# AS5600.net
KiCad netlist of a schematic drawn in Altium Designer
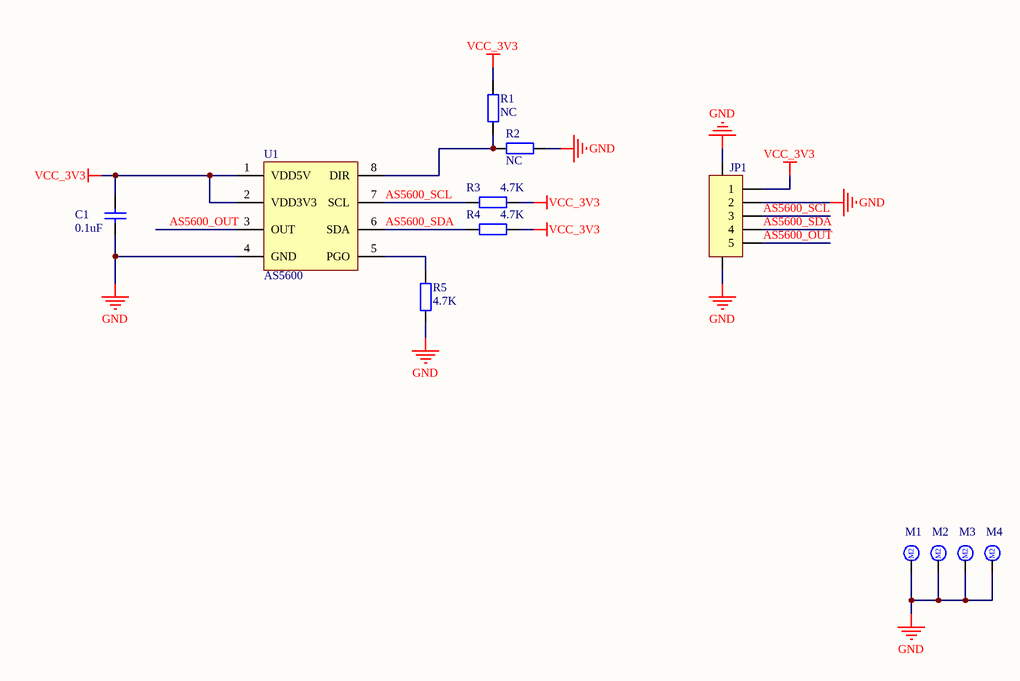
[diagram p0: AS5600.SchDoc]

(export (version "E")
  (design (tool "Eeschema 10.0.6"))
  (components
    (comp (ref "C1")
      (value "0.1uF")
      (footprint "C0402_L")
      (description "贴片电容")
      (libsource (lib "0.1 - 电阻-电容-电感-晶振-晶体-磁珠-电位器") (part "C"))
    )
    (comp (ref "JP1")
      (value "CON-5P")
      (footprint "SH1.0-WT-5P")
      (description "5P连接器")
      (libsource (lib "5.0 - 1.00mm连接器(FPC1.0-SH1.0)") (part "Header 5"))
    )
    (comp (ref "M1")
      (value "M2.5")
      (footprint "M2.5")
      (description "M2孔支撑柱")
      (libsource (lib "USER_Lib") (part "M2系列"))
    )
    (comp (ref "M2")
      (value "M2.5")
      (footprint "M2.5")
      (description "M2孔支撑柱")
      (libsource (lib "USER_Lib") (part "M2系列"))
    )
    (comp (ref "M3")
      (value "M2.5")
      (footprint "M2.5")
      (description "M2孔支撑柱")
      (libsource (lib "USER_Lib") (part "M2系列"))
    )
    (comp (ref "M4")
      (value "M2.5")
      (footprint "M2.5")
      (description "M2孔支撑柱")
      (libsource (lib "USER_Lib") (part "M2系列"))
    )
    (comp (ref "R1")
      (value "NC")
      (footprint "R0402_L")
      (description "贴片电阻")
      (libsource (lib "0.1 - 电阻-电容-电感-晶振-晶体-磁珠-电位器") (part "R"))
    )
    (comp (ref "R2")
      (value "NC")
      (footprint "R0402_L")
      (description "贴片电阻")
      (libsource (lib "0.1 - 电阻-电容-电感-晶振-晶体-磁珠-电位器") (part "R"))
    )
    (comp (ref "R3")
      (value "4.7K")
      (footprint "R0402_L")
      (description "贴片电阻")
      (libsource (lib "0.1 - 电阻-电容-电感-晶振-晶体-磁珠-电位器") (part "R"))
    )
    (comp (ref "R4")
      (value "4.7K")
      (footprint "R0402_L")
      (description "贴片电阻")
      (libsource (lib "0.1 - 电阻-电容-电感-晶振-晶体-磁珠-电位器") (part "R"))
    )
    (comp (ref "R5")
      (value "4.7K")
      (footprint "R0402_L")
      (description "贴片电阻")
      (libsource (lib "0.1 - 电阻-电容-电感-晶振-晶体-磁珠-电位器") (part "R"))
    )
    (comp (ref "U1")
      (value "AS5600")
      (footprint "SOIC-8L")
      (description "12bit 磁编码器")
      (libsource (lib "USER_Lib") (part "AS5600"))
    )
  )
  (nets
    (net (code "1") (name "/AS5600_OUT") (class "Default")
      (node (ref "JP1") (pin "5") (pinfunction "5_5") (pintype "passive"))
      (node (ref "U1") (pin "3") (pinfunction "OUT_3") (pintype "passive"))
    )
    (net (code "2") (name "/AS5600_SCL") (class "Default")
      (node (ref "JP1") (pin "3") (pinfunction "3_3") (pintype "passive"))
      (node (ref "R3") (pin "2") (pinfunction "2_2") (pintype "passive"))
      (node (ref "U1") (pin "7") (pinfunction "SCL_7") (pintype "passive"))
    )
    (net (code "3") (name "/AS5600_SDA") (class "Default")
      (node (ref "JP1") (pin "4") (pinfunction "4_4") (pintype "passive"))
      (node (ref "R4") (pin "2") (pinfunction "2_2") (pintype "passive"))
      (node (ref "U1") (pin "6") (pinfunction "SDA_6") (pintype "passive"))
    )
    (net (code "4") (name "GND") (class "Default")
      (node (ref "C1") (pin "1") (pinfunction "1_1") (pintype "passive"))
      (node (ref "JP1") (pin "0") (pinfunction "0_0") (pintype "passive"))
      (node (ref "JP1") (pin "2") (pinfunction "2_2") (pintype "passive"))
      (node (ref "M1") (pin "1") (pinfunction "1_1") (pintype "passive"))
      (node (ref "M2") (pin "1") (pinfunction "1_1") (pintype "passive"))
      (node (ref "M3") (pin "1") (pinfunction "1_1") (pintype "passive"))
      (node (ref "M4") (pin "1") (pinfunction "1_1") (pintype "passive"))
      (node (ref "R2") (pin "1") (pinfunction "1_1") (pintype "passive"))
      (node (ref "R5") (pin "2") (pinfunction "2_2") (pintype "passive"))
      (node (ref "U1") (pin "4") (pinfunction "GND_4") (pintype "passive"))
    )
    (net (code "5") (name "Net-(U1-DIR)") (class "Default")
      (node (ref "R1") (pin "1") (pinfunction "1_1") (pintype "passive"))
      (node (ref "R2") (pin "2") (pinfunction "2_2") (pintype "passive"))
      (node (ref "U1") (pin "8") (pinfunction "DIR_8") (pintype "passive"))
    )
    (net (code "6") (name "Net-(U1-PGO)") (class "Default")
      (node (ref "R5") (pin "1") (pinfunction "1_1") (pintype "passive"))
      (node (ref "U1") (pin "5") (pinfunction "PGO_5") (pintype "passive"))
    )
    (net (code "7") (name "VCC_3V3") (class "Default")
      (node (ref "C1") (pin "2") (pinfunction "2_2") (pintype "passive"))
      (node (ref "JP1") (pin "1") (pinfunction "1_1") (pintype "passive"))
      (node (ref "R1") (pin "2") (pinfunction "2_2") (pintype "passive"))
      (node (ref "R3") (pin "1") (pinfunction "1_1") (pintype "passive"))
      (node (ref "R4") (pin "1") (pinfunction "1_1") (pintype "passive"))
      (node (ref "U1") (pin "1") (pinfunction "VDD5V_1") (pintype "passive"))
      (node (ref "U1") (pin "2") (pinfunction "VDD3V3_2") (pintype "passive"))
    )
  )
)
